# untitled.net
KiCad netlist of a schematic drawn in EAGLE
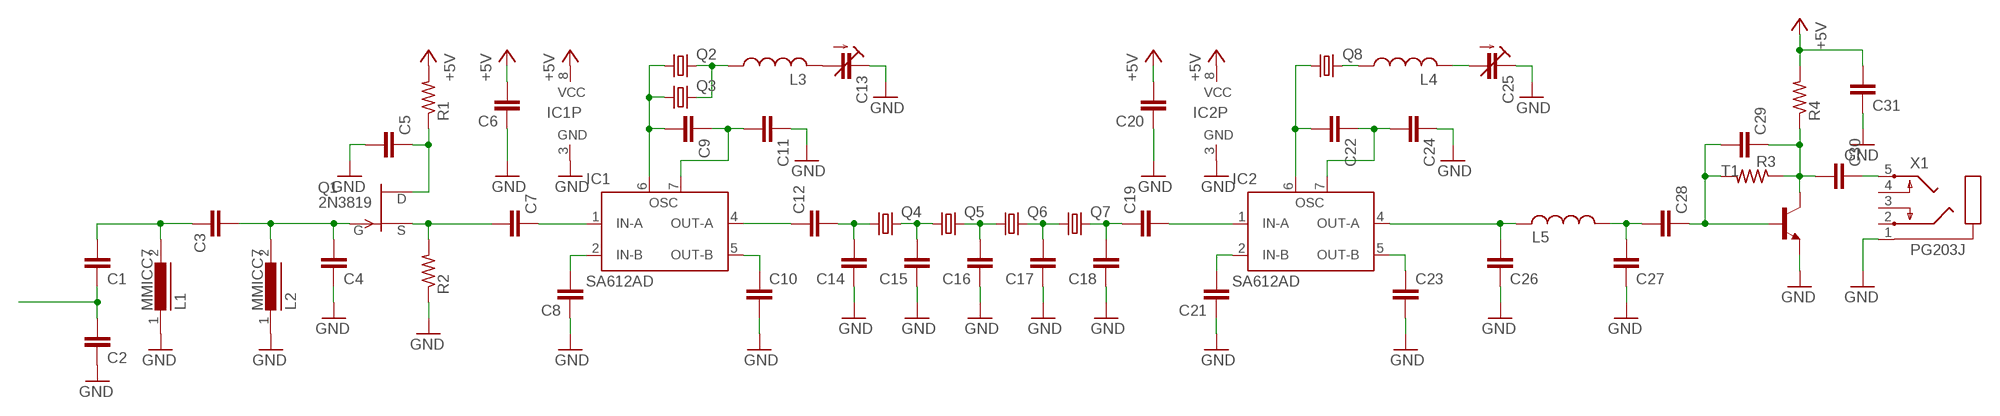
[diagram p0: schematic, sheet 1]

(export (version "E")
  (design (tool "Eeschema 10.0.6"))
  (components
    (comp (ref "C1")
      (value "C-EUC0805K")
      (footprint "eagle-import:C0805K")
      (libsource (lib "eagle-import") (part "C-EUC0805K"))
    )
    (comp (ref "C2")
      (value "C-EUC0805K")
      (footprint "eagle-import:C0805K")
      (libsource (lib "eagle-import") (part "C-EUC0805K"))
    )
    (comp (ref "C3")
      (value "C-EUC0805K")
      (footprint "eagle-import:C0805K")
      (libsource (lib "eagle-import") (part "C-EUC0805K"))
    )
    (comp (ref "C4")
      (value "C-EUC0805K")
      (footprint "eagle-import:C0805K")
      (libsource (lib "eagle-import") (part "C-EUC0805K"))
    )
    (comp (ref "C5")
      (value "C-EUC0805K")
      (footprint "eagle-import:C0805K")
      (libsource (lib "eagle-import") (part "C-EUC0805K"))
    )
    (comp (ref "C6")
      (value "C-EUC0805K")
      (footprint "eagle-import:C0805K")
      (libsource (lib "eagle-import") (part "C-EUC0805K"))
    )
    (comp (ref "C7")
      (value "C-EUC0805K")
      (footprint "eagle-import:C0805K")
      (libsource (lib "eagle-import") (part "C-EUC0805K"))
    )
    (comp (ref "C8")
      (value "C-EUC0805K")
      (footprint "eagle-import:C0805K")
      (libsource (lib "eagle-import") (part "C-EUC0805K"))
    )
    (comp (ref "C9")
      (value "C-EUC0805K")
      (footprint "eagle-import:C0805K")
      (libsource (lib "eagle-import") (part "C-EUC0805K"))
    )
    (comp (ref "C10")
      (value "C-EUC0805K")
      (footprint "eagle-import:C0805K")
      (libsource (lib "eagle-import") (part "C-EUC0805K"))
    )
    (comp (ref "C11")
      (value "C-EUC0805K")
      (footprint "eagle-import:C0805K")
      (libsource (lib "eagle-import") (part "C-EUC0805K"))
    )
    (comp (ref "C12")
      (value "C-EUC0805K")
      (footprint "eagle-import:C0805K")
      (libsource (lib "eagle-import") (part "C-EUC0805K"))
    )
    (comp (ref "C13")
      (value "C-TRIMMTZ03")
      (footprint "eagle-import:CTRIMTZ03")
      (libsource (lib "eagle-import") (part "C-TRIMMTZ03"))
    )
    (comp (ref "C14")
      (value "C-EUC0805K")
      (footprint "eagle-import:C0805K")
      (libsource (lib "eagle-import") (part "C-EUC0805K"))
    )
    (comp (ref "C15")
      (value "C-EUC0805K")
      (footprint "eagle-import:C0805K")
      (libsource (lib "eagle-import") (part "C-EUC0805K"))
    )
    (comp (ref "C16")
      (value "C-EUC0805K")
      (footprint "eagle-import:C0805K")
      (libsource (lib "eagle-import") (part "C-EUC0805K"))
    )
    (comp (ref "C17")
      (value "C-EUC0805K")
      (footprint "eagle-import:C0805K")
      (libsource (lib "eagle-import") (part "C-EUC0805K"))
    )
    (comp (ref "C18")
      (value "C-EUC0805K")
      (footprint "eagle-import:C0805K")
      (libsource (lib "eagle-import") (part "C-EUC0805K"))
    )
    (comp (ref "C19")
      (value "C-EUC0805K")
      (footprint "eagle-import:C0805K")
      (libsource (lib "eagle-import") (part "C-EUC0805K"))
    )
    (comp (ref "C20")
      (value "C-EUC0805K")
      (footprint "eagle-import:C0805K")
      (libsource (lib "eagle-import") (part "C-EUC0805K"))
    )
    (comp (ref "C21")
      (value "C-EUC0805K")
      (footprint "eagle-import:C0805K")
      (libsource (lib "eagle-import") (part "C-EUC0805K"))
    )
    (comp (ref "C22")
      (value "C-EUC0805K")
      (footprint "eagle-import:C0805K")
      (libsource (lib "eagle-import") (part "C-EUC0805K"))
    )
    (comp (ref "C23")
      (value "C-EUC0805K")
      (footprint "eagle-import:C0805K")
      (libsource (lib "eagle-import") (part "C-EUC0805K"))
    )
    (comp (ref "C24")
      (value "C-EUC0805K")
      (footprint "eagle-import:C0805K")
      (libsource (lib "eagle-import") (part "C-EUC0805K"))
    )
    (comp (ref "C25")
      (value "C-TRIMMTZ03")
      (footprint "eagle-import:CTRIMTZ03")
      (libsource (lib "eagle-import") (part "C-TRIMMTZ03"))
    )
    (comp (ref "C26")
      (value "C-EUC0805K")
      (footprint "eagle-import:C0805K")
      (libsource (lib "eagle-import") (part "C-EUC0805K"))
    )
    (comp (ref "C27")
      (value "C-EUC0805K")
      (footprint "eagle-import:C0805K")
      (libsource (lib "eagle-import") (part "C-EUC0805K"))
    )
    (comp (ref "C28")
      (value "C-EUC0805K")
      (footprint "eagle-import:C0805K")
      (libsource (lib "eagle-import") (part "C-EUC0805K"))
    )
    (comp (ref "C29")
      (value "C-EUC0805K")
      (footprint "eagle-import:C0805K")
      (libsource (lib "eagle-import") (part "C-EUC0805K"))
    )
    (comp (ref "C30")
      (value "C-EUC0805K")
      (footprint "eagle-import:C0805K")
      (libsource (lib "eagle-import") (part "C-EUC0805K"))
    )
    (comp (ref "C31")
      (value "C-EUC0805K")
      (footprint "eagle-import:C0805K")
      (libsource (lib "eagle-import") (part "C-EUC0805K"))
    )
    (comp (ref "IC1")
      (value "SA612AD")
      (footprint "eagle-import:SO08")
      (libsource (lib "eagle-import") (part "SA612AD"))
    )
    (comp (ref "IC2")
      (value "SA612AD")
      (footprint "eagle-import:SO08")
      (libsource (lib "eagle-import") (part "SA612AD"))
    )
    (comp (ref "L1")
      (value "MMICC7")
      (footprint "eagle-import:MMICC7")
      (libsource (lib "eagle-import") (part "MMICC7"))
    )
    (comp (ref "L2")
      (value "MMICC7")
      (footprint "eagle-import:MMICC7")
      (libsource (lib "eagle-import") (part "MMICC7"))
    )
    (comp (ref "L3")
      (value "L-US0204/7")
      (footprint "eagle-import:0204_7")
      (libsource (lib "eagle-import") (part "L-US0204/7"))
    )
    (comp (ref "L4")
      (value "L-US0204/7")
      (footprint "eagle-import:0204_7")
      (libsource (lib "eagle-import") (part "L-US0204/7"))
    )
    (comp (ref "L5")
      (value "L-US0204/7")
      (footprint "eagle-import:0204_7")
      (libsource (lib "eagle-import") (part "L-US0204/7"))
    )
    (comp (ref "Q1")
      (value "2N3819")
      (footprint "eagle-import:TO92")
      (libsource (lib "eagle-import") (part "2N3819"))
    )
    (comp (ref "Q2")
      (value "CRYSTALHC49S")
      (footprint "eagle-import:HC49_S")
      (libsource (lib "eagle-import") (part "CRYSTALHC49S"))
    )
    (comp (ref "Q3")
      (value "CRYSTALHC49S")
      (footprint "eagle-import:HC49_S")
      (libsource (lib "eagle-import") (part "CRYSTALHC49S"))
    )
    (comp (ref "Q4")
      (value "CRYSTALHC49S")
      (footprint "eagle-import:HC49_S")
      (libsource (lib "eagle-import") (part "CRYSTALHC49S"))
    )
    (comp (ref "Q5")
      (value "CRYSTALHC49S")
      (footprint "eagle-import:HC49_S")
      (libsource (lib "eagle-import") (part "CRYSTALHC49S"))
    )
    (comp (ref "Q6")
      (value "CRYSTALHC49S")
      (footprint "eagle-import:HC49_S")
      (libsource (lib "eagle-import") (part "CRYSTALHC49S"))
    )
    (comp (ref "Q7")
      (value "CRYSTALHC49S")
      (footprint "eagle-import:HC49_S")
      (libsource (lib "eagle-import") (part "CRYSTALHC49S"))
    )
    (comp (ref "Q8")
      (value "CRYSTALHC49S")
      (footprint "eagle-import:HC49_S")
      (libsource (lib "eagle-import") (part "CRYSTALHC49S"))
    )
    (comp (ref "R1")
      (value "R-US_R0805")
      (footprint "eagle-import:R0805")
      (libsource (lib "eagle-import") (part "R-US_R0805"))
    )
    (comp (ref "R2")
      (value "R-US_R0805")
      (footprint "eagle-import:R0805")
      (libsource (lib "eagle-import") (part "R-US_R0805"))
    )
    (comp (ref "R3")
      (value "R-US_R0805")
      (footprint "eagle-import:R0805")
      (libsource (lib "eagle-import") (part "R-US_R0805"))
    )
    (comp (ref "R4")
      (value "R-US_R0805")
      (footprint "eagle-import:R0805")
      (libsource (lib "eagle-import") (part "R-US_R0805"))
    )
    (comp (ref "T1")
      (value "MMBT3904LT1-NPN-SOT23-BEC")
      (footprint "eagle-import:SOT23-BEC")
      (libsource (lib "eagle-import") (part "-NPN-SOT23-BECMMBT3904LT1"))
    )
    (comp (ref "X1")
      (value "PG203J")
      (footprint "eagle-import:PG203J")
      (libsource (lib "eagle-import") (part "PG203J"))
    )
  )
  (nets
    (net (code "1") (name "+5V") (class "Default")
      (node (ref "C20") (pin "2") (pinfunction "2_2") (pintype "passive"))
      (node (ref "C31") (pin "2") (pinfunction "2_2") (pintype "passive"))
      (node (ref "C6") (pin "2") (pinfunction "2_2") (pintype "passive"))
      (node (ref "IC1") (pin "8") (pinfunction "VCC_8") (pintype "power_in"))
      (node (ref "IC2") (pin "8") (pinfunction "VCC_8") (pintype "power_in"))
      (node (ref "R1") (pin "2") (pinfunction "2_2") (pintype "passive"))
      (node (ref "R4") (pin "2") (pinfunction "2_2") (pintype "passive"))
    )
    (net (code "2") (name "GND") (class "Default")
      (node (ref "C10") (pin "2") (pinfunction "2_2") (pintype "passive"))
      (node (ref "C11") (pin "1") (pinfunction "1_1") (pintype "passive"))
      (node (ref "C13") (pin "1") (pinfunction "E_1") (pintype "passive"))
      (node (ref "C14") (pin "1") (pinfunction "1_1") (pintype "passive"))
      (node (ref "C15") (pin "1") (pinfunction "1_1") (pintype "passive"))
      (node (ref "C16") (pin "1") (pinfunction "1_1") (pintype "passive"))
      (node (ref "C17") (pin "1") (pinfunction "1_1") (pintype "passive"))
      (node (ref "C18") (pin "1") (pinfunction "1_1") (pintype "passive"))
      (node (ref "C2") (pin "1") (pinfunction "1_1") (pintype "passive"))
      (node (ref "C20") (pin "1") (pinfunction "1_1") (pintype "passive"))
      (node (ref "C21") (pin "1") (pinfunction "1_1") (pintype "passive"))
      (node (ref "C23") (pin "2") (pinfunction "2_2") (pintype "passive"))
      (node (ref "C24") (pin "1") (pinfunction "1_1") (pintype "passive"))
      (node (ref "C25") (pin "1") (pinfunction "E_1") (pintype "passive"))
      (node (ref "C26") (pin "1") (pinfunction "1_1") (pintype "passive"))
      (node (ref "C27") (pin "1") (pinfunction "1_1") (pintype "passive"))
      (node (ref "C31") (pin "1") (pinfunction "1_1") (pintype "passive"))
      (node (ref "C4") (pin "1") (pinfunction "1_1") (pintype "passive"))
      (node (ref "C5") (pin "2") (pinfunction "2_2") (pintype "passive"))
      (node (ref "C6") (pin "1") (pinfunction "1_1") (pintype "passive"))
      (node (ref "C8") (pin "1") (pinfunction "1_1") (pintype "passive"))
      (node (ref "IC1") (pin "3") (pinfunction "GND_3") (pintype "power_in"))
      (node (ref "IC2") (pin "3") (pinfunction "GND_3") (pintype "power_in"))
      (node (ref "L1") (pin "1") (pinfunction "1_1") (pintype "passive"))
      (node (ref "L2") (pin "1") (pinfunction "1_1") (pintype "passive"))
      (node (ref "R2") (pin "1") (pinfunction "1_1") (pintype "passive"))
      (node (ref "T1") (pin "E") (pinfunction "E_E") (pintype "passive"))
      (node (ref "X1") (pin "1") (pinfunction "1_1") (pintype "passive"))
    )
    (net (code "3") (name "Net-(C1-Pad1)") (class "Default")
      (node (ref "C1") (pin "1") (pinfunction "1_1") (pintype "passive"))
      (node (ref "C2") (pin "2") (pinfunction "2_2") (pintype "passive"))
    )
    (net (code "4") (name "Net-(C1-Pad2)") (class "Default")
      (node (ref "C1") (pin "2") (pinfunction "2_2") (pintype "passive"))
      (node (ref "C3") (pin "1") (pinfunction "1_1") (pintype "passive"))
      (node (ref "L1") (pin "2") (pinfunction "2_2") (pintype "passive"))
    )
    (net (code "5") (name "Net-(C12-Pad2)") (class "Default")
      (node (ref "C12") (pin "2") (pinfunction "2_2") (pintype "passive"))
      (node (ref "C14") (pin "2") (pinfunction "2_2") (pintype "passive"))
      (node (ref "Q4") (pin "1") (pinfunction "1_1") (pintype "passive"))
    )
    (net (code "6") (name "Net-(C13-A)") (class "Default")
      (node (ref "C13") (pin "2") (pinfunction "A_2") (pintype "passive"))
      (node (ref "L3") (pin "2") (pinfunction "2_2") (pintype "passive"))
    )
    (net (code "7") (name "Net-(C15-Pad2)") (class "Default")
      (node (ref "C15") (pin "2") (pinfunction "2_2") (pintype "passive"))
      (node (ref "Q4") (pin "2") (pinfunction "2_2") (pintype "passive"))
      (node (ref "Q5") (pin "1") (pinfunction "1_1") (pintype "passive"))
    )
    (net (code "8") (name "Net-(C16-Pad2)") (class "Default")
      (node (ref "C16") (pin "2") (pinfunction "2_2") (pintype "passive"))
      (node (ref "Q5") (pin "2") (pinfunction "2_2") (pintype "passive"))
      (node (ref "Q6") (pin "1") (pinfunction "1_1") (pintype "passive"))
    )
    (net (code "9") (name "Net-(C17-Pad2)") (class "Default")
      (node (ref "C17") (pin "2") (pinfunction "2_2") (pintype "passive"))
      (node (ref "Q6") (pin "2") (pinfunction "2_2") (pintype "passive"))
      (node (ref "Q7") (pin "1") (pinfunction "1_1") (pintype "passive"))
    )
    (net (code "10") (name "Net-(C18-Pad2)") (class "Default")
      (node (ref "C18") (pin "2") (pinfunction "2_2") (pintype "passive"))
      (node (ref "C19") (pin "1") (pinfunction "1_1") (pintype "passive"))
      (node (ref "Q7") (pin "2") (pinfunction "2_2") (pintype "passive"))
    )
    (net (code "11") (name "Net-(C25-A)") (class "Default")
      (node (ref "C25") (pin "2") (pinfunction "A_2") (pintype "passive"))
      (node (ref "L4") (pin "2") (pinfunction "2_2") (pintype "passive"))
    )
    (net (code "12") (name "Net-(C27-Pad2)") (class "Default")
      (node (ref "C27") (pin "2") (pinfunction "2_2") (pintype "passive"))
      (node (ref "C28") (pin "2") (pinfunction "2_2") (pintype "passive"))
      (node (ref "L5") (pin "1") (pinfunction "1_1") (pintype "passive"))
    )
    (net (code "13") (name "Net-(C28-Pad1)") (class "Default")
      (node (ref "C28") (pin "1") (pinfunction "1_1") (pintype "passive"))
      (node (ref "C29") (pin "2") (pinfunction "2_2") (pintype "passive"))
      (node (ref "R3") (pin "2") (pinfunction "2_2") (pintype "passive"))
      (node (ref "T1") (pin "B") (pinfunction "B_B") (pintype "passive"))
    )
    (net (code "14") (name "Net-(C29-Pad1)") (class "Default")
      (node (ref "C29") (pin "1") (pinfunction "1_1") (pintype "passive"))
      (node (ref "C30") (pin "2") (pinfunction "2_2") (pintype "passive"))
      (node (ref "R3") (pin "1") (pinfunction "1_1") (pintype "passive"))
      (node (ref "R4") (pin "1") (pinfunction "1_1") (pintype "passive"))
      (node (ref "T1") (pin "C") (pinfunction "C_C") (pintype "passive"))
    )
    (net (code "15") (name "Net-(C30-Pad1)") (class "Default")
      (node (ref "C30") (pin "1") (pinfunction "1_1") (pintype "passive"))
      (node (ref "X1") (pin "5") (pinfunction "5_5") (pintype "passive"))
    )
    (net (code "16") (name "Net-(IC1A-IN-A)") (class "Default")
      (node (ref "C7") (pin "1") (pinfunction "1_1") (pintype "passive"))
      (node (ref "IC1") (pin "1") (pinfunction "IN-A_1") (pintype "input"))
    )
    (net (code "17") (name "Net-(IC1A-IN-B)") (class "Default")
      (node (ref "C8") (pin "2") (pinfunction "2_2") (pintype "passive"))
      (node (ref "IC1") (pin "2") (pinfunction "IN-B_2") (pintype "input"))
    )
    (net (code "18") (name "Net-(IC1A-OSC')") (class "Default")
      (node (ref "C11") (pin "2") (pinfunction "2_2") (pintype "passive"))
      (node (ref "C9") (pin "1") (pinfunction "1_1") (pintype "passive"))
      (node (ref "IC1") (pin "7") (pinfunction "OSC'_7") (pintype "passive"))
    )
    (net (code "19") (name "Net-(IC1A-OSC)") (class "Default")
      (node (ref "C9") (pin "2") (pinfunction "2_2") (pintype "passive"))
      (node (ref "IC1") (pin "6") (pinfunction "OSC_6") (pintype "passive"))
      (node (ref "Q2") (pin "1") (pinfunction "1_1") (pintype "passive"))
      (node (ref "Q3") (pin "1") (pinfunction "1_1") (pintype "passive"))
    )
    (net (code "20") (name "Net-(IC1A-OUT-A)") (class "Default")
      (node (ref "C12") (pin "1") (pinfunction "1_1") (pintype "passive"))
      (node (ref "IC1") (pin "4") (pinfunction "OUT-A_4") (pintype "input"))
    )
    (net (code "21") (name "Net-(IC1A-OUT-B)") (class "Default")
      (node (ref "C10") (pin "1") (pinfunction "1_1") (pintype "passive"))
      (node (ref "IC1") (pin "5") (pinfunction "OUT-B_5") (pintype "input"))
    )
    (net (code "22") (name "Net-(IC2A-IN-A)") (class "Default")
      (node (ref "C19") (pin "2") (pinfunction "2_2") (pintype "passive"))
      (node (ref "IC2") (pin "1") (pinfunction "IN-A_1") (pintype "input"))
    )
    (net (code "23") (name "Net-(IC2A-IN-B)") (class "Default")
      (node (ref "C21") (pin "2") (pinfunction "2_2") (pintype "passive"))
      (node (ref "IC2") (pin "2") (pinfunction "IN-B_2") (pintype "input"))
    )
    (net (code "24") (name "Net-(IC2A-OSC')") (class "Default")
      (node (ref "C22") (pin "1") (pinfunction "1_1") (pintype "passive"))
      (node (ref "C24") (pin "2") (pinfunction "2_2") (pintype "passive"))
      (node (ref "IC2") (pin "7") (pinfunction "OSC'_7") (pintype "passive"))
    )
    (net (code "25") (name "Net-(IC2A-OSC)") (class "Default")
      (node (ref "C22") (pin "2") (pinfunction "2_2") (pintype "passive"))
      (node (ref "IC2") (pin "6") (pinfunction "OSC_6") (pintype "passive"))
      (node (ref "Q8") (pin "1") (pinfunction "1_1") (pintype "passive"))
    )
    (net (code "26") (name "Net-(IC2A-OUT-A)") (class "Default")
      (node (ref "C26") (pin "2") (pinfunction "2_2") (pintype "passive"))
      (node (ref "IC2") (pin "4") (pinfunction "OUT-A_4") (pintype "input"))
      (node (ref "L5") (pin "2") (pinfunction "2_2") (pintype "passive"))
    )
    (net (code "27") (name "Net-(IC2A-OUT-B)") (class "Default")
      (node (ref "C23") (pin "1") (pinfunction "1_1") (pintype "passive"))
      (node (ref "IC2") (pin "5") (pinfunction "OUT-B_5") (pintype "input"))
    )
    (net (code "28") (name "Net-(L3-Pad1)") (class "Default")
      (node (ref "L3") (pin "1") (pinfunction "1_1") (pintype "passive"))
      (node (ref "Q2") (pin "2") (pinfunction "2_2") (pintype "passive"))
      (node (ref "Q3") (pin "2") (pinfunction "2_2") (pintype "passive"))
    )
    (net (code "29") (name "Net-(L4-Pad1)") (class "Default")
      (node (ref "L4") (pin "1") (pinfunction "1_1") (pintype "passive"))
      (node (ref "Q8") (pin "2") (pinfunction "2_2") (pintype "passive"))
    )
    (net (code "30") (name "Net-(Q1-D)") (class "Default")
      (node (ref "C5") (pin "1") (pinfunction "1_1") (pintype "passive"))
      (node (ref "Q1") (pin "1") (pinfunction "D_1") (pintype "passive"))
      (node (ref "R1") (pin "1") (pinfunction "1_1") (pintype "passive"))
    )
    (net (code "31") (name "Net-(Q1-G)") (class "Default")
      (node (ref "C3") (pin "2") (pinfunction "2_2") (pintype "passive"))
      (node (ref "C4") (pin "2") (pinfunction "2_2") (pintype "passive"))
      (node (ref "L2") (pin "2") (pinfunction "2_2") (pintype "passive"))
      (node (ref "Q1") (pin "2") (pinfunction "G_2") (pintype "passive"))
    )
    (net (code "32") (name "Net-(Q1-S)") (class "Default")
      (node (ref "C7") (pin "2") (pinfunction "2_2") (pintype "passive"))
      (node (ref "Q1") (pin "3") (pinfunction "S_3") (pintype "passive"))
      (node (ref "R2") (pin "2") (pinfunction "2_2") (pintype "passive"))
    )
    (net (code "33") (name "unconnected-(X1-Pad2)") (class "Default")
      (node (ref "X1") (pin "2") (pinfunction "2_2") (pintype "passive"))
    )
    (net (code "34") (name "unconnected-(X1-Pad3)") (class "Default")
      (node (ref "X1") (pin "3") (pinfunction "3_3") (pintype "passive"))
    )
    (net (code "35") (name "unconnected-(X1-Pad4)") (class "Default")
      (node (ref "X1") (pin "4") (pinfunction "4_4") (pintype "passive"))
    )
  )
)
